# water-meter-v1.net
KiCad netlist of a schematic drawn in EasyEDA Pro
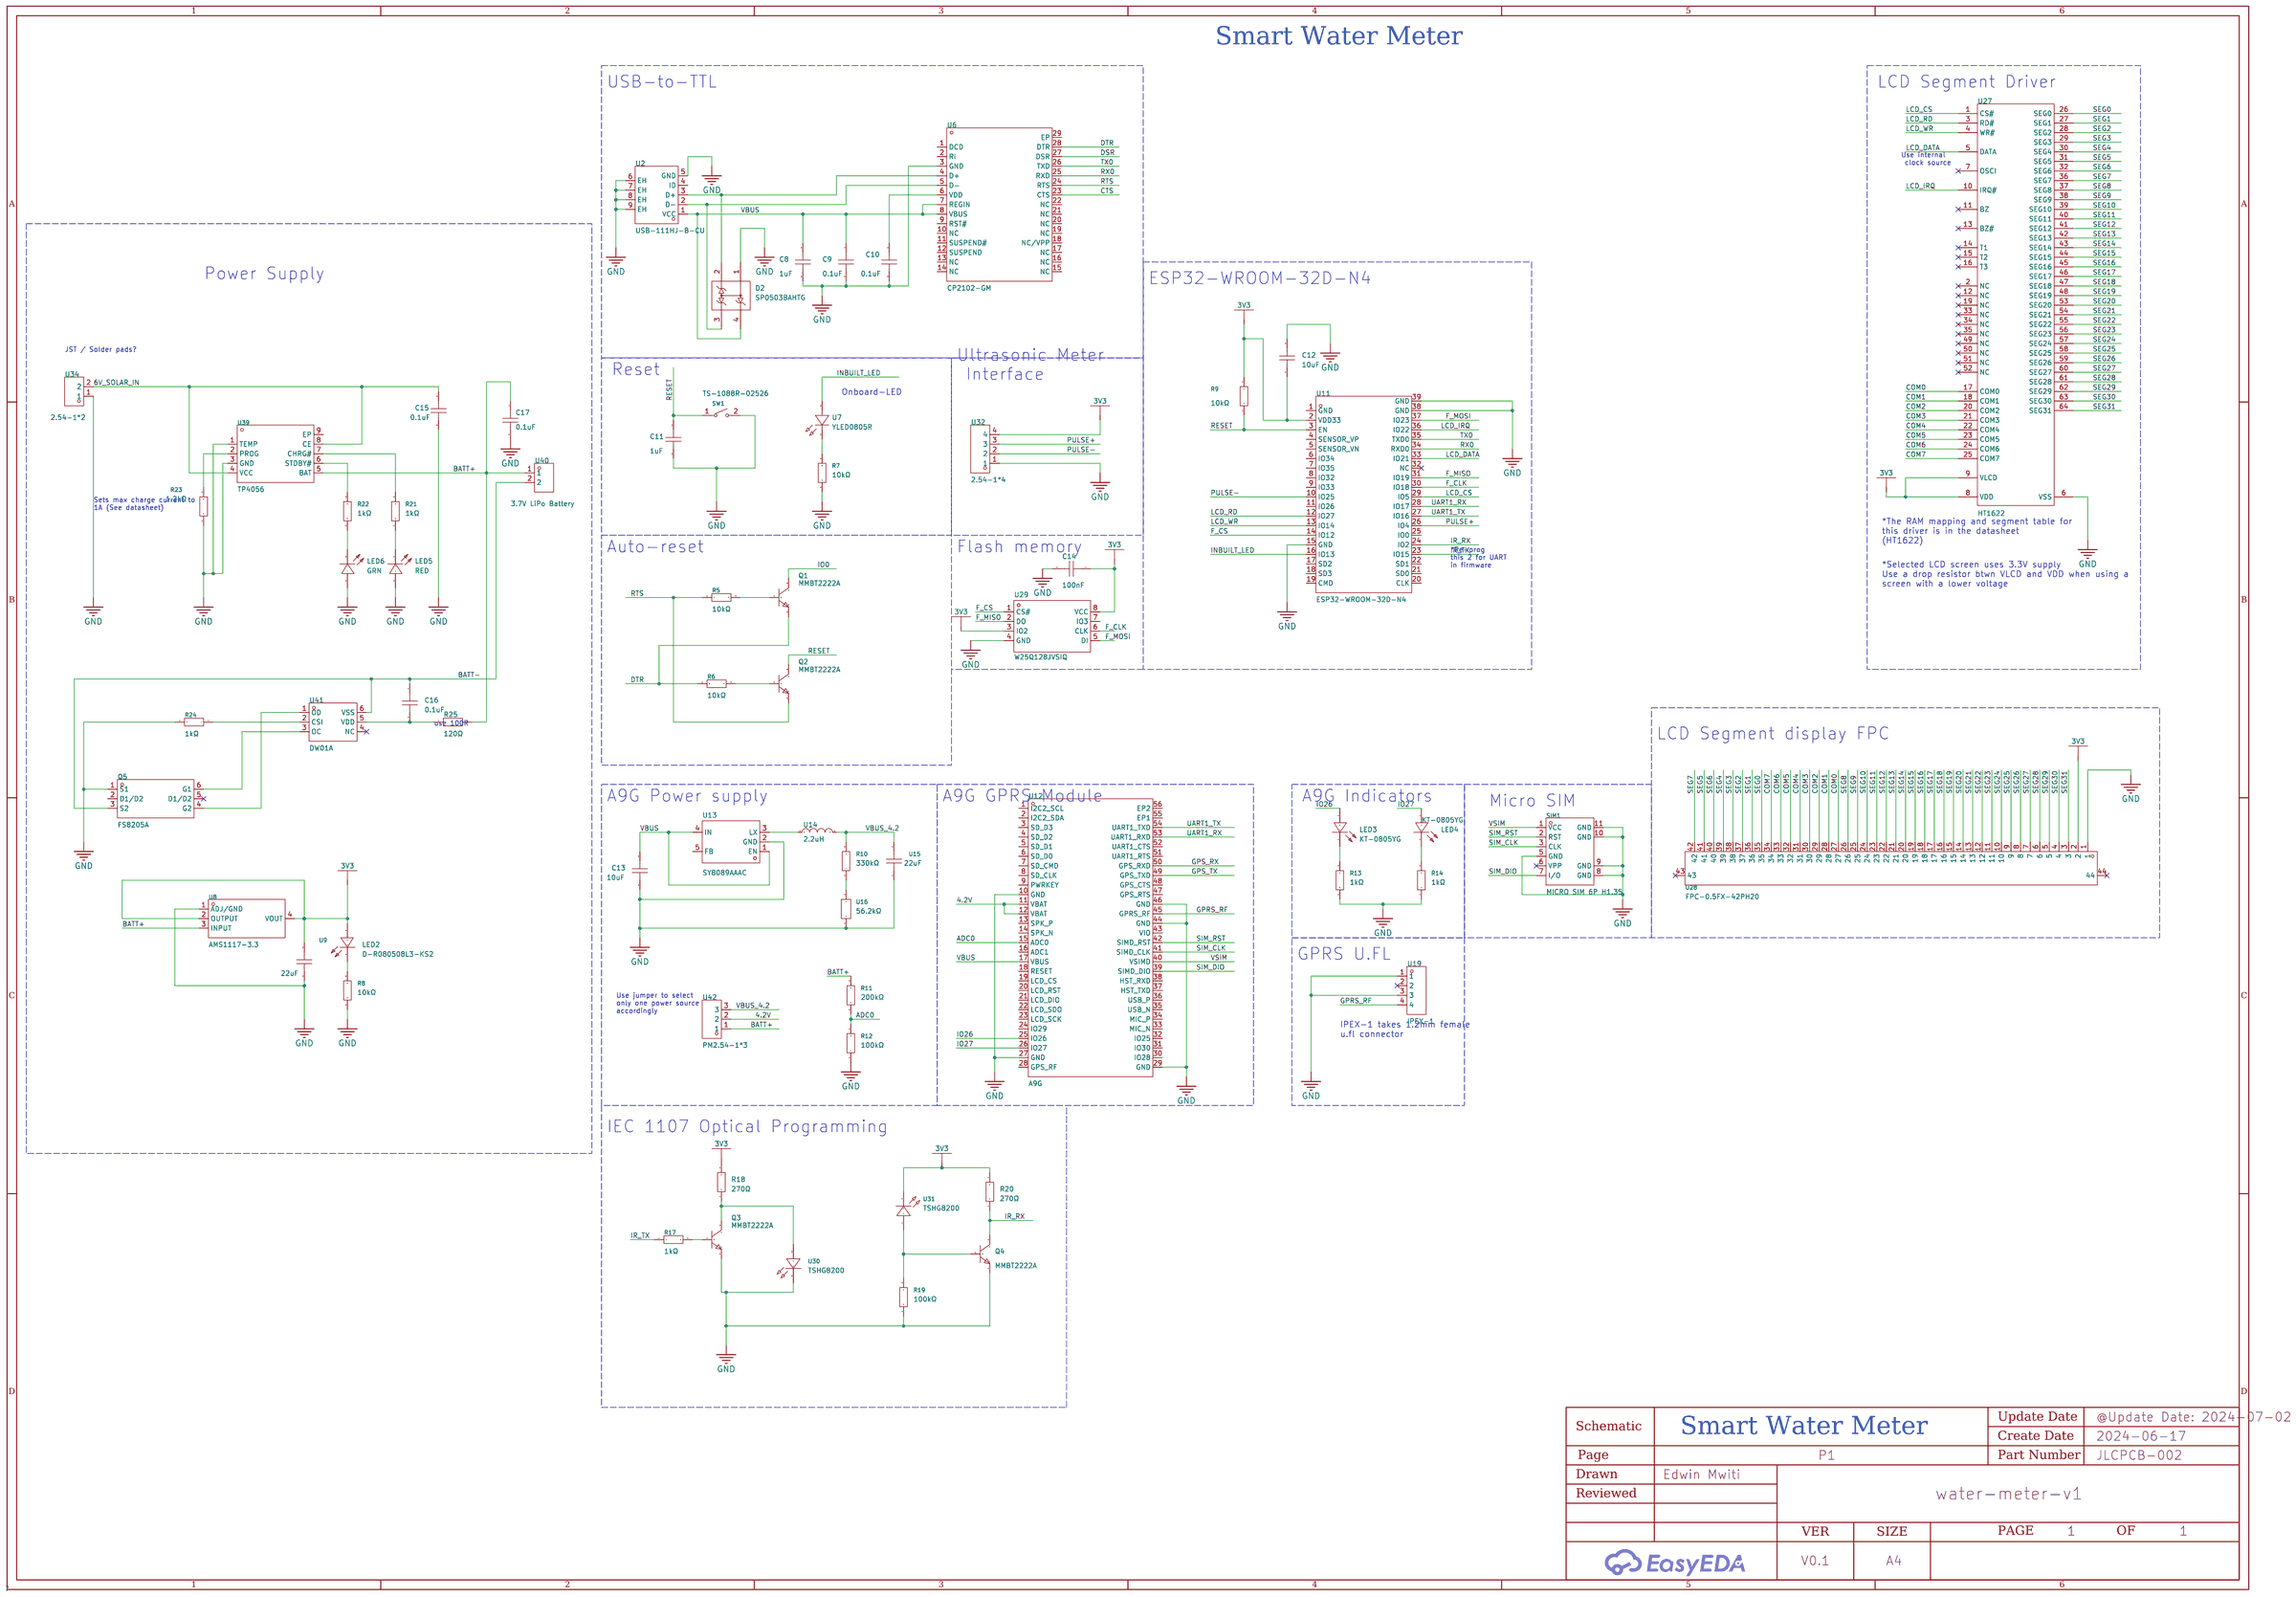
[diagram p0: schematic sheet]

(export (version "E")
  (design (tool "Eeschema 10.0.6"))
  (components
    (comp (ref "C8") (value "1uF") (footprint "easyedapro:C0805") (libsource (lib "easyedapro") (part "CAP")))
    (comp (ref "C9")
      (value "0.1uF")
      (footprint "easyedapro:C0805")
      (libsource (lib "easyedapro") (part "CAP"))
    )
    (comp (ref "C10")
      (value "0.1uF")
      (footprint "easyedapro:C0805")
      (libsource (lib "easyedapro") (part "CAP"))
    )
    (comp (ref "C11")
      (value "1uF")
      (footprint "easyedapro:C0805")
      (libsource (lib "easyedapro") (part "CAP"))
    )
    (comp (ref "C12")
      (value "10uF")
      (footprint "easyedapro:C0805")
      (fields
        (field (name "Manufacturer Part") "C0805X6S106K250NT")
        (field (name "Manufacturer") "SANYEAR(叁叶源)")
      )
      (libsource (lib "easyedapro") (part "C0805X6S106K250NT"))
    )
    (comp (ref "C13")
      (value "10uF")
      (footprint "easyedapro:C0805")
      (fields
        (field (name "Manufacturer Part") "C0805X6S106K250NT")
        (field (name "Manufacturer") "SANYEAR(叁叶源)")
      )
      (libsource (lib "easyedapro") (part "C0805X6S106K250NT"))
    )
    (comp (ref "C14")
      (value "100nF")
      (footprint "easyedapro:C0805")
      (fields
        (field (name "Manufacturer Part") "MBK0805X7R104K500NT")
        (field (name "Manufacturer") "FH-BK(风华邦科)")
      )
      (libsource (lib "easyedapro") (part "0805B104K500NT_C2830721"))
    )
    (comp (ref "C15")
      (value "0.1uF")
      (footprint "easyedapro:C0805")
      (libsource (lib "easyedapro") (part "CAP"))
    )
    (comp (ref "C16")
      (value "0.1uF")
      (footprint "easyedapro:C0805")
      (libsource (lib "easyedapro") (part "CAP"))
    )
    (comp (ref "C17")
      (value "0.1uF")
      (footprint "easyedapro:C0805")
      (libsource (lib "easyedapro") (part "CAP"))
    )
    (comp (ref "D2")
      (value "SP0503BAHTG")
      (footprint "easyedapro:SOT-143-4_L2.9-W1.3-P1.92-LS2.4-BL")
      (description "Type:ESD")
      (fields (field (name "Manufacturer") "TECH PUBLIC(台舟)"))
      (libsource (lib "easyedapro") (part "SP0503BAHTG_C3040626"))
    )
    (comp (ref "LED2")
      (value "D-R080508L3-KS2")
      (footprint "easyedapro:LED0805-RD")
      (description "Emitted Color:Red")
      (fields (field (name "Manufacturer") "ARKLED(方舟)"))
      (libsource (lib "easyedapro") (part "D-R080508L3-KS2"))
    )
    (comp (ref "LED3")
      (value "KT-0805YG")
      (footprint "easyedapro:LED0805-R-RD")
      (description "Emitted Color:Green-yellow")
      (fields (field (name "Manufacturer") "KENTO"))
      (libsource (lib "easyedapro") (part "Yellow green 0805"))
    )
    (comp (ref "LED4")
      (value "KT-0805YG")
      (footprint "easyedapro:LED0805-R-RD")
      (description "Emitted Color:Green-yellow")
      (fields (field (name "Manufacturer") "KENTO"))
      (libsource (lib "easyedapro") (part "Yellow green 0805"))
    )
    (comp (ref "LED5")
      (value "RED")
      (footprint "easyedapro:LED0805-RD")
      (description "Emitted Color:Red")
      (fields (field (name "Manufacturer") "ARKLED(方舟)"))
      (libsource (lib "easyedapro") (part "D-R080508L3-KS2"))
    )
    (comp (ref "LED6")
      (value "GRN")
      (footprint "easyedapro:LED0805-R-RD_GREEN")
      (description "Emitted Color:Green-yellow")
      (fields (field (name "Manufacturer") "yongyu(永裕光电)"))
      (libsource (lib "easyedapro") (part "SZYY0805YG"))
    )
    (comp (ref "Q1")
      (value "MMBT2222A")
      (footprint "easyedapro:SOT-23-3_L2.9-W1.3-P1.90-LS2.4-BR")
      (fields (field (name "Manufacturer") "WPMtek(维攀)"))
      (libsource (lib "easyedapro") (part "MMBT2222A_C2688232"))
    )
    (comp (ref "Q2")
      (value "MMBT2222A")
      (footprint "easyedapro:SOT-23-3_L2.9-W1.3-P1.90-LS2.4-BR")
      (fields (field (name "Manufacturer") "WPMtek(维攀)"))
      (libsource (lib "easyedapro") (part "MMBT2222A_C2688232"))
    )
    (comp (ref "Q3")
      (value "MMBT2222A")
      (footprint "easyedapro:SOT-23-3_L2.9-W1.3-P1.90-LS2.4-BR")
      (fields (field (name "Manufacturer") "WPMtek(维攀)"))
      (libsource (lib "easyedapro") (part "MMBT2222A_C2688232"))
    )
    (comp (ref "Q4")
      (value "MMBT2222A")
      (footprint "easyedapro:SOT-23-3_L2.9-W1.3-P1.90-LS2.4-BR")
      (fields (field (name "Manufacturer") "WPMtek(维攀)"))
      (libsource (lib "easyedapro") (part "MMBT2222A_C2688232"))
    )
    (comp (ref "Q5")
      (value "FS8205A")
      (footprint "easyedapro:SOT-23-6_L2.9-W1.6-P0.95-LS2.8-BR")
      (fields (field (name "Manufacturer") "FUXINSEMI(富芯森美)"))
      (libsource (lib "easyedapro") (part "FS8205A_C908265"))
    )
    (comp (ref "R5")
      (value "10kΩ")
      (footprint "easyedapro:R0805")
      (fields (field (name "Manufacturer Part") "RMC080510K1%N") (field (name "Manufacturer") "Tyohm(幸亚电阻)"))
      (libsource (lib "easyedapro") (part "RMC080510K1%N"))
    )
    (comp (ref "R6")
      (value "10kΩ")
      (footprint "easyedapro:R0805")
      (fields (field (name "Manufacturer Part") "RMC080510K1%N") (field (name "Manufacturer") "Tyohm(幸亚电阻)"))
      (libsource (lib "easyedapro") (part "RMC080510K1%N"))
    )
    (comp (ref "R7")
      (value "10kΩ")
      (footprint "easyedapro:R0805")
      (fields (field (name "Manufacturer Part") "RMC080510K1%N") (field (name "Manufacturer") "Tyohm(幸亚电阻)"))
      (libsource (lib "easyedapro") (part "RMC080510K1%N"))
    )
    (comp (ref "R8")
      (value "10kΩ")
      (footprint "easyedapro:R0805")
      (fields (field (name "Manufacturer Part") "RMC080510K1%N") (field (name "Manufacturer") "Tyohm(幸亚电阻)"))
      (libsource (lib "easyedapro") (part "RMC080510K1%N"))
    )
    (comp (ref "R9")
      (value "10kΩ")
      (footprint "easyedapro:R0805")
      (fields (field (name "Manufacturer Part") "RMC080510K1%N") (field (name "Manufacturer") "Tyohm(幸亚电阻)"))
      (libsource (lib "easyedapro") (part "RMC080510K1%N"))
    )
    (comp (ref "R10")
      (value "330kΩ")
      (footprint "easyedapro:R0805")
      (fields (field (name "Manufacturer Part") "RMC0805330K5%N") (field (name "Manufacturer") "Tyohm(幸亚电阻)"))
      (libsource (lib "easyedapro") (part "RMC0805330K5%N"))
    )
    (comp (ref "R11")
      (value "200kΩ")
      (footprint "easyedapro:R0805")
      (fields (field (name "Manufacturer Part") "RMC0805200K1%N") (field (name "Manufacturer") "Tyohm(幸亚电阻)"))
      (libsource (lib "easyedapro") (part "RMC0805200K1%N"))
    )
    (comp (ref "R12")
      (value "100kΩ")
      (footprint "easyedapro:R0805")
      (fields (field (name "Manufacturer Part") "RMC0805100K1%N") (field (name "Manufacturer") "Tyohm(幸亚电阻)"))
      (libsource (lib "easyedapro") (part "RMC0805100K1%N"))
    )
    (comp (ref "R13")
      (value "1kΩ")
      (footprint "easyedapro:R0805")
      (fields (field (name "Manufacturer Part") "RMC08051K1%N") (field (name "Manufacturer") "Tyohm(幸亚电阻)"))
      (libsource (lib "easyedapro") (part "RMC08051K1%N"))
    )
    (comp (ref "R14")
      (value "1kΩ")
      (footprint "easyedapro:R0805")
      (fields (field (name "Manufacturer Part") "RMC08051K1%N") (field (name "Manufacturer") "Tyohm(幸亚电阻)"))
      (libsource (lib "easyedapro") (part "RMC08051K1%N"))
    )
    (comp (ref "R17")
      (value "1kΩ")
      (footprint "easyedapro:R0805")
      (fields (field (name "Manufacturer Part") "RMC08051K5%N") (field (name "Manufacturer") "Tyohm(幸亚电阻)"))
      (libsource (lib "easyedapro") (part "RMC08051K5%N"))
    )
    (comp (ref "R18")
      (value "270Ω")
      (footprint "easyedapro:R0805")
      (fields (field (name "Manufacturer Part") "RC0805JR-07270RL") (field (name "Manufacturer") "YAGEO(国巨)"))
      (libsource (lib "easyedapro") (part "RC0805JR-07270RL"))
    )
    (comp (ref "R19")
      (value "100kΩ")
      (footprint "easyedapro:R0805")
      (fields (field (name "Manufacturer Part") "RMC0805100K1%N") (field (name "Manufacturer") "Tyohm(幸亚电阻)"))
      (libsource (lib "easyedapro") (part "RMC0805100K1%N"))
    )
    (comp (ref "R20")
      (value "270Ω")
      (footprint "easyedapro:R0805")
      (fields (field (name "Manufacturer Part") "RC0805JR-07270RL") (field (name "Manufacturer") "YAGEO(国巨)"))
      (libsource (lib "easyedapro") (part "RC0805JR-07270RL"))
    )
    (comp (ref "R21")
      (value "1kΩ")
      (footprint "easyedapro:R0805")
      (fields (field (name "Manufacturer Part") "RMC08051K5%N") (field (name "Manufacturer") "Tyohm(幸亚电阻)"))
      (libsource (lib "easyedapro") (part "RMC08051K5%N"))
    )
    (comp (ref "R22")
      (value "1kΩ")
      (footprint "easyedapro:R0805")
      (fields (field (name "Manufacturer Part") "RMC08051K5%N") (field (name "Manufacturer") "Tyohm(幸亚电阻)"))
      (libsource (lib "easyedapro") (part "RMC08051K5%N"))
    )
    (comp (ref "R23")
      (value "1.2kΩ")
      (footprint "easyedapro:R0805")
      (fields (field (name "Manufacturer Part") "RMC08051.2K5%N") (field (name "Manufacturer") "Tyohm(幸亚电阻)"))
      (libsource (lib "easyedapro") (part "RMC08051.2K5%N"))
    )
    (comp (ref "R24")
      (value "1kΩ")
      (footprint "easyedapro:R0805")
      (fields (field (name "Manufacturer Part") "RMC08051K5%N") (field (name "Manufacturer") "Tyohm(幸亚电阻)"))
      (libsource (lib "easyedapro") (part "RMC08051K5%N"))
    )
    (comp (ref "R25")
      (value "120Ω")
      (footprint "easyedapro:R0805")
      (fields
        (field (name "Manufacturer Part") "RMC 0805 120R J N")
        (field (name "Manufacturer") "Tyohm(幸亚电阻)")
      )
      (libsource (lib "easyedapro") (part "RMC08051205%N"))
    )
    (comp (ref "SIM1")
      (value "MICRO SIM 6P H1.35")
      (footprint "easyedapro:SIM-SMD_MICRO-SIM-6P-H1.35")
      (fields (field (name "Manufacturer") "SHOU HAN(首韩)"))
      (libsource (lib "easyedapro") (part "MICRO SIM 6P H1.35"))
    )
    (comp (ref "SW1")
      (value "TS-1088R-02526")
      (footprint "easyedapro:SW-SMD_L3.9-W3.0-P4.45")
      (fields (field (name "Manufacturer") "XUNPU(讯普)"))
      (libsource (lib "easyedapro") (part "TS-1088R-02526"))
    )
    (comp (ref "U2")
      (value "USB-111HJ-B-CU")
      (footprint "easyedapro:MICRO-USB-SMD_HOOYA_USB-111HJ-B-CU")
      (description "Number of Contacts:5P")
      (fields (field (name "Manufacturer") "HOOYA(皓宇电子)"))
      (libsource (lib "easyedapro") (part "USB-111HJ-B-CU"))
    )
    (comp (ref "U6")
      (value "CP2102-GM")
      (footprint "easyedapro:QFN-28_L5.0-W5.0-P0.50-TL-EP3.2")
      (fields (field (name "Manufacturer") "SKYWORKS/SILICON LABS(芯科)"))
      (libsource (lib "easyedapro") (part "CP2102-GM"))
    )
    (comp (ref "U7")
      (value "YLED0805R")
      (footprint "easyedapro:LED0805-RD")
      (fields (field (name "Manufacturer") "YONGYUTAI(永裕泰)"))
      (libsource (lib "easyedapro") (part "YLED0805R"))
    )
    (comp (ref "U8")
      (value "AMS1117-3.3")
      (footprint "easyedapro:SOT-223-3_L6.5-W3.4-P2.30-LS7.0-BR")
      (fields (field (name "Manufacturer") "TECH PUBLIC(台舟)"))
      (libsource (lib "easyedapro") (part "AMS1117-3.3_C18212698"))
    )
    (comp (ref "U9")
      (value "22uF")
      (footprint "easyedapro:C0805")
      (fields
        (field (name "Manufacturer Part") "V226M0805X5R100NHP")
        (field (name "Manufacturer") "VIIYONG(微容)")
      )
      (libsource (lib "easyedapro") (part "V226M0805X5R100NHP"))
    )
    (comp (ref "U11")
      (value "ESP32-WROOM-32D-N4")
      (footprint "easyedapro:WIFIM-SMD_39P-L25.5-W18.0-P1.27-BL")
      (fields (field (name "Manufacturer") "ESPRESSIF(乐鑫)"))
      (libsource (lib "easyedapro") (part "ESP32-WROOM-32D"))
    )
    (comp (ref "U12")
      (value "A9G")
      (footprint "easyedapro:GSM-SMD_A9-GSM-GPRSMODULE")
      (fields (field (name "Manufacturer") "Ai-Thinker(安信可)"))
      (libsource (lib "easyedapro") (part "A9G"))
    )
    (comp (ref "U13")
      (value "SY8089AAAC")
      (footprint "easyedapro:SOT-23-5_L3.0-W1.7-P0.95-LS2.8-BR")
      (fields (field (name "Manufacturer") "silergy(矽力杰)"))
      (libsource (lib "easyedapro") (part "SY8089AAAC"))
    )
    (comp (ref "U14")
      (value "2.2uH")
      (footprint "easyedapro:IND-SMD_L4.5-W4.0_SLF0403-1")
      (fields (field (name "Manufacturer Part") "CY43-2.2UH") (field (name "Manufacturer") "SHOU HAN(首韩)"))
      (libsource (lib "easyedapro") (part "CY43-2.2UH"))
    )
    (comp (ref "U15")
      (value "22uF")
      (footprint "easyedapro:C0805")
      (fields
        (field (name "Manufacturer Part") "V226M0805X5R100NHP")
        (field (name "Manufacturer") "VIIYONG(微容)")
      )
      (libsource (lib "easyedapro") (part "V226M0805X5R100NHP"))
    )
    (comp (ref "U16")
      (value "56.2kΩ")
      (footprint "easyedapro:R0805")
      (fields (field (name "Manufacturer Part") "SCR0805F56K2") (field (name "Manufacturer") "VO(翔胜)"))
      (libsource (lib "easyedapro") (part "SCR0805F56K2"))
    )
    (comp (ref "U19")
      (value "IPEX-1")
      (footprint "easyedapro:IPEX-SMD_4P-L2.6-W2.6-LS3.0")
      (description "RF Series:IPEX")
      (fields (field (name "Manufacturer") "Ziisor(致哲)"))
      (libsource (lib "easyedapro") (part "IPEX-1"))
    )
    (comp (ref "U27")
      (value "HT1622")
      (footprint "easyedapro:LQFP-64_L7.0-W7.0-P0.40-LS9.2-BL")
      (fields (field (name "Manufacturer") "HOLTEK(合泰/盛群)"))
      (libsource (lib "easyedapro") (part "HT1622_C46302"))
    )
    (comp (ref "U28")
      (value "FPC-0.5FX-42PH20")
      (footprint "easyedapro:FPC-SMD_42P-P0.50_YUANDI_FPC-0.5FX-42PH20")
      (description "Locking Feature:Clamshell Contact Type:Bottom Contact Number of Contacts:42P Pitch:0.5mm")
      (fields (field (name "Manufacturer") "Yuandi(元迪)"))
      (libsource (lib "easyedapro") (part "FPC-0.5FX-42PH20"))
    )
    (comp (ref "U29")
      (value "W25Q128JVSIQ")
      (footprint "easyedapro:SOIC-8_L5.3-W5.3-P1.27-LS8.0-BL")
      (fields (field (name "Manufacturer") "WINBOND(华邦)"))
      (libsource (lib "easyedapro") (part "W25Q128JVSIQTR"))
    )
    (comp (ref "U30")
      (value "TSHG8200")
      (footprint "easyedapro:LED-TH_BD5.0-P2.54-FD-1")
      (fields (field (name "Manufacturer") "VISHAY(威世)"))
      (libsource (lib "easyedapro") (part "TSHG8200"))
    )
    (comp (ref "U31")
      (value "TSHG8200")
      (footprint "easyedapro:LED-TH_BD5.0-P2.54-FD-1")
      (fields (field (name "Manufacturer") "VISHAY(威世)"))
      (libsource (lib "easyedapro") (part "TSHG8200"))
    )
    (comp (ref "U32")
      (value "2.54-1*4")
      (footprint "easyedapro:HDR-TH_4P-P2.54-V-M-1")
      (description "Pin Structure:1x4P Pitch:2.54mm Number of Rows:Plugin Number of Pins:4P")
      (fields (field (name "Manufacturer") "ZHOURI(洲日)"))
      (libsource (lib "easyedapro") (part "2.54-1*4"))
    )
    (comp (ref "U34")
      (value "2.54-1*2")
      (footprint "easyedapro:HDR-TH_2P-P2.54-V-M")
      (description "Pin Structure:1x2P Pitch:2.54mm Number of Rows:Plugin Number of Pins:2P Contact Plating:Gold")
      (fields (field (name "Manufacturer") "ZHOURI(洲日)"))
      (libsource (lib "easyedapro") (part "2.54-1*2"))
    )
    (comp (ref "U39")
      (value "TP4056")
      (footprint "easyedapro:ESOP-8_L4.9-W3.9-P1.27-LS6.0-BL-EP")
      (fields (field (name "Manufacturer") "TPOWER(天源)"))
      (libsource (lib "easyedapro") (part "TP4056_C382139"))
    )
    (comp (ref "U40")
      (value "3.7V LiPo Battery")
      (footprint "easyedapro:HDR-TH_2P-P2.54-V-M")
      (description "Pin Structure:1x2P Pitch:2.54mm Number of Rows:Plugin Number of Pins:2P Contact Plating:Gold")
      (fields (field (name "Manufacturer") "ZHOURI(洲日)"))
      (libsource (lib "easyedapro") (part "2.54-1*2"))
    )
    (comp (ref "U41")
      (value "DW01A")
      (footprint "easyedapro:SOT-23-6_L2.9-W1.6-P0.95-LS2.8-BL")
      (fields (field (name "Manufacturer") "YONGYUTAI(永裕泰)"))
      (libsource (lib "easyedapro") (part "DW01A_C2927799"))
    )
    (comp (ref "U42")
      (value "PM2.54-1*3")
      (footprint "easyedapro:HDR-TH_3P-P2.54-V-F")
      (fields (field (name "Manufacturer") "ZHOURI(洲日)"))
      (libsource (lib "easyedapro") (part "PM2.54-1*3"))
    )
  )
  (nets
    (net (code "1") (name "/4.2V") (class "Default")
      (node (ref "U12") (pin "11") (pinfunction "VBAT_11") (pintype "unspecified"))
      (node (ref "U12") (pin "12") (pinfunction "VBAT_12") (pintype "unspecified"))
      (node (ref "U42") (pin "2") (pinfunction "2_2") (pintype "unspecified"))
    )
    (net (code "2") (name "/6V_SOLAR_IN") (class "Default")
      (node (ref "C15") (pin "1") (pinfunction "1_1") (pintype "input"))
      (node (ref "U34") (pin "2") (pinfunction "2_2") (pintype "unspecified"))
      (node (ref "U39") (pin "4") (pinfunction "VCC_4") (pintype "input"))
      (node (ref "U39") (pin "8") (pinfunction "CE_8") (pintype "input"))
    )
    (net (code "3") (name "/ADC0") (class "Default")
      (node (ref "R11") (pin "1") (pinfunction "1_1") (pintype "input"))
      (node (ref "R12") (pin "2") (pinfunction "2_2") (pintype "input"))
      (node (ref "U12") (pin "15") (pinfunction "ADC0_15") (pintype "unspecified"))
    )
    (net (code "4") (name "/BATT+") (class "Default")
      (node (ref "C17") (pin "1") (pinfunction "1_1") (pintype "input"))
      (node (ref "R11") (pin "2") (pinfunction "2_2") (pintype "input"))
      (node (ref "R25") (pin "2") (pinfunction "2_2") (pintype "input"))
      (node (ref "U39") (pin "5") (pinfunction "BAT_5") (pintype "input"))
      (node (ref "U40") (pin "1") (pinfunction "1_1") (pintype "unspecified"))
      (node (ref "U42") (pin "1") (pinfunction "1_1") (pintype "unspecified"))
      (node (ref "U8") (pin "3") (pinfunction "INPUT_3") (pintype "input"))
    )
    (net (code "5") (name "/BATT-") (class "Default")
      (node (ref "C16") (pin "1") (pinfunction "1_1") (pintype "input"))
      (node (ref "Q5") (pin "3") (pinfunction "S2_3") (pintype "unspecified"))
      (node (ref "U40") (pin "2") (pinfunction "2_2") (pintype "unspecified"))
      (node (ref "U41") (pin "6") (pinfunction "VSS_6") (pintype "unspecified"))
    )
    (net (code "6") (name "/COM0") (class "Default")
      (node (ref "U27") (pin "17") (pinfunction "COM0_17") (pintype "output"))
      (node (ref "U28") (pin "27") (pinfunction "27_27") (pintype "input"))
    )
    (net (code "7") (name "/COM1") (class "Default")
      (node (ref "U27") (pin "18") (pinfunction "COM1_18") (pintype "output"))
      (node (ref "U28") (pin "28") (pinfunction "28_28") (pintype "input"))
    )
    (net (code "8") (name "/COM2") (class "Default")
      (node (ref "U27") (pin "20") (pinfunction "COM2_20") (pintype "output"))
      (node (ref "U28") (pin "29") (pinfunction "29_29") (pintype "input"))
    )
    (net (code "9") (name "/COM3") (class "Default")
      (node (ref "U27") (pin "21") (pinfunction "COM3_21") (pintype "output"))
      (node (ref "U28") (pin "30") (pinfunction "30_30") (pintype "input"))
    )
    (net (code "10") (name "/COM4") (class "Default")
      (node (ref "U27") (pin "22") (pinfunction "COM4_22") (pintype "output"))
      (node (ref "U28") (pin "31") (pinfunction "31_31") (pintype "input"))
    )
    (net (code "11") (name "/COM5") (class "Default")
      (node (ref "U27") (pin "23") (pinfunction "COM5_23") (pintype "output"))
      (node (ref "U28") (pin "32") (pinfunction "32_32") (pintype "input"))
    )
    (net (code "12") (name "/COM6") (class "Default")
      (node (ref "U27") (pin "24") (pinfunction "COM6_24") (pintype "output"))
      (node (ref "U28") (pin "33") (pinfunction "33_33") (pintype "input"))
    )
    (net (code "13") (name "/COM7") (class "Default")
      (node (ref "U27") (pin "25") (pinfunction "COM7_25") (pintype "output"))
      (node (ref "U28") (pin "34") (pinfunction "34_34") (pintype "input"))
    )
    (net (code "14") (name "/CTS") (class "Default")
      (node (ref "U6") (pin "23") (pinfunction "CTS_23") (pintype "unspecified"))
    )
    (net (code "15") (name "/DSR") (class "Default")
      (node (ref "U6") (pin "27") (pinfunction "DSR_27") (pintype "unspecified"))
    )
    (net (code "16") (name "/DTR") (class "Default")
      (node (ref "Q1") (pin "2") (pinfunction "E_2") (pintype "input"))
      (node (ref "R6") (pin "1") (pinfunction "1_1") (pintype "input"))
      (node (ref "U6") (pin "28") (pinfunction "DTR_28") (pintype "unspecified"))
    )
    (net (code "17") (name "/F_CLK") (class "Default")
      (node (ref "U11") (pin "30") (pinfunction "IO18_30") (pintype "unspecified"))
      (node (ref "U29") (pin "6") (pinfunction "CLK_6") (pintype "unspecified"))
    )
    (net (code "18") (name "/F_CS") (class "Default")
      (node (ref "U11") (pin "14") (pinfunction "IO12_14") (pintype "unspecified"))
      (node (ref "U29") (pin "1") (pinfunction "CS#_1") (pintype "unspecified"))
    )
    (net (code "19") (name "/F_MISO") (class "Default")
      (node (ref "U11") (pin "31") (pinfunction "IO19_31") (pintype "unspecified"))
      (node (ref "U29") (pin "2") (pinfunction "DO_2") (pintype "unspecified"))
    )
    (net (code "20") (name "/F_MOSI") (class "Default")
      (node (ref "U11") (pin "37") (pinfunction "IO23_37") (pintype "unspecified"))
      (node (ref "U29") (pin "5") (pinfunction "DI_5") (pintype "unspecified"))
    )
    (net (code "21") (name "/GPRS_RF") (class "Default")
      (node (ref "U12") (pin "45") (pinfunction "GPRS_RF_45") (pintype "unspecified"))
      (node (ref "U19") (pin "4") (pinfunction "4_4") (pintype "unspecified"))
    )
    (net (code "22") (name "/GPS_RX") (class "Default")
      (node (ref "U12") (pin "50") (pinfunction "GPS_RXD_50") (pintype "unspecified"))
    )
    (net (code "23") (name "/GPS_TX") (class "Default")
      (node (ref "U12") (pin "49") (pinfunction "GPS_TXD_49") (pintype "unspecified"))
    )
    (net (code "24") (name "/INBUILT_LED") (class "Default")
      (node (ref "U11") (pin "16") (pinfunction "IO13_16") (pintype "unspecified"))
      (node (ref "U7") (pin "2") (pinfunction "A_2") (pintype "unspecified"))
    )
    (net (code "25") (name "/IO0") (class "Default")
      (node (ref "Q1") (pin "3") (pinfunction "C_3") (pintype "input"))
    )
    (net (code "26") (name "/IO26") (class "Default")
      (node (ref "LED3") (pin "1") (pinfunction "A_1") (pintype "unspecified"))
      (node (ref "U12") (pin "25") (pinfunction "IO26_25") (pintype "unspecified"))
    )
    (net (code "27") (name "/IO27") (class "Default")
      (node (ref "LED4") (pin "1") (pinfunction "A_1") (pintype "unspecified"))
      (node (ref "U12") (pin "26") (pinfunction "IO27_26") (pintype "unspecified"))
    )
    (net (code "28") (name "/IR_RX") (class "Default")
      (node (ref "Q4") (pin "3") (pinfunction "C_3") (pintype "input"))
      (node (ref "R20") (pin "1") (pinfunction "1_1") (pintype "input"))
      (node (ref "U11") (pin "24") (pinfunction "IO2_24") (pintype "unspecified"))
    )
    (net (code "29") (name "/IR_TX") (class "Default")
      (node (ref "R17") (pin "1") (pinfunction "1_1") (pintype "input"))
      (node (ref "U11") (pin "23") (pinfunction "IO15_23") (pintype "unspecified"))
    )
    (net (code "30") (name "/LCD_CS") (class "Default")
      (node (ref "U11") (pin "29") (pinfunction "IO5_29") (pintype "unspecified"))
      (node (ref "U27") (pin "1") (pinfunction "CS#_1") (pintype "unspecified"))
    )
    (net (code "31") (name "/LCD_DATA") (class "Default")
      (node (ref "U11") (pin "33") (pinfunction "IO21_33") (pintype "unspecified"))
      (node (ref "U27") (pin "5") (pinfunction "DATA_5") (pintype "bidirectional"))
    )
    (net (code "32") (name "/LCD_IRQ") (class "Default")
      (node (ref "U11") (pin "36") (pinfunction "IO22_36") (pintype "unspecified"))
      (node (ref "U27") (pin "10") (pinfunction "IRQ#_10") (pintype "unspecified"))
    )
    (net (code "33") (name "/LCD_RD") (class "Default")
      (node (ref "U11") (pin "12") (pinfunction "IO27_12") (pintype "unspecified"))
      (node (ref "U27") (pin "3") (pinfunction "RD#_3") (pintype "unspecified"))
    )
    (net (code "34") (name "/LCD_WR") (class "Default")
      (node (ref "U11") (pin "13") (pinfunction "IO14_13") (pintype "unspecified"))
      (node (ref "U27") (pin "4") (pinfunction "WR#_4") (pintype "unspecified"))
    )
    (net (code "35") (name "/PULSE+") (class "Default")
      (node (ref "U11") (pin "26") (pinfunction "IO4_26") (pintype "unspecified"))
      (node (ref "U32") (pin "3") (pinfunction "3_3") (pintype "unspecified"))
    )
    (net (code "36") (name "/PULSE-") (class "Default")
      (node (ref "U11") (pin "10") (pinfunction "IO25_10") (pintype "unspecified"))
      (node (ref "U32") (pin "2") (pinfunction "2_2") (pintype "unspecified"))
    )
    (net (code "37") (name "/RESET") (class "Default")
      (node (ref "C11") (pin "1") (pinfunction "1_1") (pintype "input"))
      (node (ref "Q2") (pin "3") (pinfunction "C_3") (pintype "input"))
      (node (ref "R9") (pin "1") (pinfunction "1_1") (pintype "input"))
      (node (ref "SW1") (pin "1") (pinfunction "1_1") (pintype "input"))
      (node (ref "U11") (pin "3") (pinfunction "EN_3") (pintype "unspecified"))
    )
    (net (code "38") (name "/RTS") (class "Default")
      (node (ref "Q2") (pin "2") (pinfunction "E_2") (pintype "input"))
      (node (ref "R5") (pin "1") (pinfunction "1_1") (pintype "input"))
      (node (ref "U6") (pin "24") (pinfunction "RTS_24") (pintype "unspecified"))
    )
    (net (code "39") (name "/RX0") (class "Default")
      (node (ref "U11") (pin "34") (pinfunction "RXD0_34") (pintype "unspecified"))
      (node (ref "U6") (pin "25") (pinfunction "RXD_25") (pintype "unspecified"))
    )
    (net (code "40") (name "/SEG0") (class "Default")
      (node (ref "U27") (pin "26") (pinfunction "SEG0_26") (pintype "output"))
      (node (ref "U28") (pin "35") (pinfunction "35_35") (pintype "input"))
    )
    (net (code "41") (name "/SEG1") (class "Default")
      (node (ref "U27") (pin "27") (pinfunction "SEG1_27") (pintype "output"))
      (node (ref "U28") (pin "36") (pinfunction "36_36") (pintype "input"))
    )
    (net (code "42") (name "/SEG2") (class "Default")
      (node (ref "U27") (pin "28") (pinfunction "SEG2_28") (pintype "output"))
      (node (ref "U28") (pin "37") (pinfunction "37_37") (pintype "input"))
    )
    (net (code "43") (name "/SEG3") (class "Default")
      (node (ref "U27") (pin "29") (pinfunction "SEG3_29") (pintype "output"))
      (node (ref "U28") (pin "38") (pinfunction "38_38") (pintype "input"))
    )
    (net (code "44") (name "/SEG4") (class "Default")
      (node (ref "U27") (pin "30") (pinfunction "SEG4_30") (pintype "output"))
      (node (ref "U28") (pin "39") (pinfunction "39_39") (pintype "input"))
    )
    (net (code "45") (name "/SEG5") (class "Default")
      (node (ref "U27") (pin "31") (pinfunction "SEG5_31") (pintype "output"))
      (node (ref "U28") (pin "41") (pinfunction "41_41") (pintype "input"))
    )
    (net (code "46") (name "/SEG6") (class "Default")
      (node (ref "U27") (pin "32") (pinfunction "SEG6_32") (pintype "output"))
      (node (ref "U28") (pin "40") (pinfunction "40_40") (pintype "input"))
    )
    (net (code "47") (name "/SEG7") (class "Default")
      (node (ref "U27") (pin "36") (pinfunction "SEG7_36") (pintype "output"))
      (node (ref "U28") (pin "42") (pinfunction "42_42") (pintype "input"))
    )
    (net (code "48") (name "/SEG8") (class "Default")
      (node (ref "U27") (pin "37") (pinfunction "SEG8_37") (pintype "output"))
      (node (ref "U28") (pin "26") (pinfunction "26_26") (pintype "input"))
    )
    (net (code "49") (name "/SEG9") (class "Default")
      (node (ref "U27") (pin "38") (pinfunction "SEG9_38") (pintype "output"))
      (node (ref "U28") (pin "25") (pinfunction "25_25") (pintype "input"))
    )
    (net (code "50") (name "/SEG10") (class "Default")
      (node (ref "U27") (pin "39") (pinfunction "SEG10_39") (pintype "output"))
      (node (ref "U28") (pin "24") (pinfunction "24_24") (pintype "input"))
    )
    (net (code "51") (name "/SEG11") (class "Default")
      (node (ref "U27") (pin "40") (pinfunction "SEG11_40") (pintype "output"))
      (node (ref "U28") (pin "23") (pinfunction "23_23") (pintype "input"))
    )
    (net (code "52") (name "/SEG12") (class "Default")
      (node (ref "U27") (pin "41") (pinfunction "SEG12_41") (pintype "output"))
      (node (ref "U28") (pin "22") (pinfunction "22_22") (pintype "input"))
    )
    (net (code "53") (name "/SEG13") (class "Default")
      (node (ref "U27") (pin "42") (pinfunction "SEG13_42") (pintype "output"))
      (node (ref "U28") (pin "21") (pinfunction "21_21") (pintype "input"))
    )
    (net (code "54") (name "/SEG14") (class "Default")
      (node (ref "U27") (pin "43") (pinfunction "SEG14_43") (pintype "output"))
      (node (ref "U28") (pin "20") (pinfunction "20_20") (pintype "input"))
    )
    (net (code "55") (name "/SEG15") (class "Default")
      (node (ref "U27") (pin "44") (pinfunction "SEG15_44") (pintype "output"))
      (node (ref "U28") (pin "19") (pinfunction "19_19") (pintype "input"))
    )
    (net (code "56") (name "/SEG16") (class "Default")
      (node (ref "U27") (pin "45") (pinfunction "SEG16_45") (pintype "output"))
      (node (ref "U28") (pin "18") (pinfunction "18_18") (pintype "input"))
    )
    (net (code "57") (name "/SEG17") (class "Default")
      (node (ref "U27") (pin "46") (pinfunction "SEG17_46") (pintype "output"))
      (node (ref "U28") (pin "17") (pinfunction "17_17") (pintype "input"))
    )
    (net (code "58") (name "/SEG18") (class "Default")
      (node (ref "U27") (pin "47") (pinfunction "SEG18_47") (pintype "output"))
      (node (ref "U28") (pin "16") (pinfunction "16_16") (pintype "input"))
    )
    (net (code "59") (name "/SEG19") (class "Default")
      (node (ref "U27") (pin "48") (pinfunction "SEG19_48") (pintype "output"))
      (node (ref "U28") (pin "15") (pinfunction "15_15") (pintype "input"))
    )
    (net (code "60") (name "/SEG20") (class "Default")
      (node (ref "U27") (pin "53") (pinfunction "SEG20_53") (pintype "output"))
      (node (ref "U28") (pin "14") (pinfunction "14_14") (pintype "input"))
    )
    (net (code "61") (name "/SEG21") (class "Default")
      (node (ref "U27") (pin "54") (pinfunction "SEG21_54") (pintype "output"))
      (node (ref "U28") (pin "13") (pinfunction "13_13") (pintype "input"))
    )
    (net (code "62") (name "/SEG22") (class "Default")
      (node (ref "U27") (pin "55") (pinfunction "SEG22_55") (pintype "output"))
      (node (ref "U28") (pin "12") (pinfunction "12_12") (pintype "input"))
    )
    (net (code "63") (name "/SEG23") (class "Default")
      (node (ref "U27") (pin "56") (pinfunction "SEG23_56") (pintype "output"))
      (node (ref "U28") (pin "11") (pinfunction "11_11") (pintype "input"))
    )
    (net (code "64") (name "/SEG24") (class "Default")
      (node (ref "U27") (pin "57") (pinfunction "SEG24_57") (pintype "output"))
      (node (ref "U28") (pin "10") (pinfunction "10_10") (pintype "input"))
    )
    (net (code "65") (name "/SEG25") (class "Default")
      (node (ref "U27") (pin "58") (pinfunction "SEG25_58") (pintype "output"))
      (node (ref "U28") (pin "9") (pinfunction "9_9") (pintype "input"))
    )
    (net (code "66") (name "/SEG26") (class "Default")
      (node (ref "U27") (pin "59") (pinfunction "SEG26_59") (pintype "output"))
      (node (ref "U28") (pin "8") (pinfunction "8_8") (pintype "input"))
    )
    (net (code "67") (name "/SEG27") (class "Default")
      (node (ref "U27") (pin "60") (pinfunction "SEG27_60") (pintype "output"))
      (node (ref "U28") (pin "7") (pinfunction "7_7") (pintype "input"))
    )
    (net (code "68") (name "/SEG28") (class "Default")
      (node (ref "U27") (pin "61") (pinfunction "SEG28_61") (pintype "output"))
      (node (ref "U28") (pin "6") (pinfunction "6_6") (pintype "input"))
    )
    (net (code "69") (name "/SEG29") (class "Default")
      (node (ref "U27") (pin "62") (pinfunction "SEG29_62") (pintype "output"))
      (node (ref "U28") (pin "5") (pinfunction "5_5") (pintype "input"))
    )
    (net (code "70") (name "/SEG30") (class "Default")
      (node (ref "U27") (pin "63") (pinfunction "SEG30_63") (pintype "output"))
      (node (ref "U28") (pin "4") (pinfunction "4_4") (pintype "input"))
    )
    (net (code "71") (name "/SEG31") (class "Default")
      (node (ref "U27") (pin "64") (pinfunction "SEG31_64") (pintype "output"))
      (node (ref "U28") (pin "3") (pinfunction "3_3") (pintype "input"))
    )
    (net (code "72") (name "/SIM_CLK") (class "Default")
      (node (ref "SIM1") (pin "3") (pinfunction "CLK_3") (pintype "input"))
      (node (ref "U12") (pin "41") (pinfunction "SIMD_CLK_41") (pintype "unspecified"))
    )
    (net (code "73") (name "/SIM_DIO") (class "Default")
      (node (ref "SIM1") (pin "7") (pinfunction "I/O_7") (pintype "input"))
      (node (ref "U12") (pin "39") (pinfunction "SIMD_DIO_39") (pintype "unspecified"))
    )
    (net (code "74") (name "/SIM_RST") (class "Default")
      (node (ref "SIM1") (pin "2") (pinfunction "RST_2") (pintype "input"))
      (node (ref "U12") (pin "42") (pinfunction "SIMD_RST_42") (pintype "unspecified"))
    )
    (net (code "75") (name "/TX0") (class "Default")
      (node (ref "U11") (pin "35") (pinfunction "TXD0_35") (pintype "unspecified"))
      (node (ref "U6") (pin "26") (pinfunction "TXD_26") (pintype "unspecified"))
    )
    (net (code "76") (name "/UART1_RX") (class "Default")
      (node (ref "U11") (pin "28") (pinfunction "IO17_28") (pintype "unspecified"))
      (node (ref "U12") (pin "53") (pinfunction "UART1_RXD_53") (pintype "unspecified"))
    )
    (net (code "77") (name "/UART1_TX") (class "Default")
      (node (ref "U11") (pin "27") (pinfunction "IO16_27") (pintype "unspecified"))
      (node (ref "U12") (pin "54") (pinfunction "UART1_TXD_54") (pintype "unspecified"))
    )
    (net (code "78") (name "/VBUS") (class "Default")
      (node (ref "C13") (pin "2") (pinfunction "2_2") (pintype "input"))
      (node (ref "C8") (pin "1") (pinfunction "1_1") (pintype "input"))
      (node (ref "C9") (pin "1") (pinfunction "1_1") (pintype "input"))
      (node (ref "D2") (pin "4") (pinfunction "4_4") (pintype "input"))
      (node (ref "U12") (pin "17") (pinfunction "VBUS_17") (pintype "unspecified"))
      (node (ref "U13") (pin "1") (pinfunction "EN_1") (pintype "unspecified"))
      (node (ref "U13") (pin "4") (pinfunction "IN_4") (pintype "unspecified"))
      (node (ref "U2") (pin "1") (pinfunction "VCC_1") (pintype "unspecified"))
      (node (ref "U6") (pin "7") (pinfunction "REGIN_7") (pintype "unspecified"))
      (node (ref "U6") (pin "8") (pinfunction "VBUS_8") (pintype "unspecified"))
    )
    (net (code "79") (name "/VBUS_4.2") (class "Default")
      (node (ref "R10") (pin "2") (pinfunction "2_2") (pintype "input"))
      (node (ref "U14") (pin "2") (pinfunction "2_2") (pintype "unspecified"))
      (node (ref "U15") (pin "2") (pinfunction "2_2") (pintype "input"))
      (node (ref "U42") (pin "3") (pinfunction "3_3") (pintype "unspecified"))
    )
    (net (code "80") (name "/VSIM") (class "Default")
      (node (ref "SIM1") (pin "1") (pinfunction "VCC_1") (pintype "input"))
      (node (ref "U12") (pin "40") (pinfunction "VSIMD_40") (pintype "unspecified"))
    )
    (net (code "81") (name "3V3") (class "Default")
      (node (ref "C12") (pin "1") (pinfunction "1_1") (pintype "input"))
      (node (ref "C14") (pin "1") (pinfunction "1_1") (pintype "unspecified"))
      (node (ref "LED2") (pin "2") (pinfunction "A_2") (pintype "unspecified"))
      (node (ref "R18") (pin "2") (pinfunction "2_2") (pintype "input"))
      (node (ref "R20") (pin "2") (pinfunction "2_2") (pintype "input"))
      (node (ref "R9") (pin "2") (pinfunction "2_2") (pintype "input"))
      (node (ref "U11") (pin "2") (pinfunction "VDD33_2") (pintype "unspecified"))
      (node (ref "U27") (pin "8") (pinfunction "VDD_8") (pintype "unspecified"))
      (node (ref "U27") (pin "9") (pinfunction "VLCD_9") (pintype "unspecified"))
      (node (ref "U28") (pin "2") (pinfunction "2_2") (pintype "input"))
      (node (ref "U29") (pin "3") (pinfunction "IO2_3") (pintype "unspecified"))
      (node (ref "U29") (pin "8") (pinfunction "VCC_8") (pintype "unspecified"))
      (node (ref "U31") (pin "2") (pinfunction "C_2") (pintype "input"))
      (node (ref "U32") (pin "4") (pinfunction "4_4") (pintype "unspecified"))
      (node (ref "U8") (pin "2") (pinfunction "OUTPUT_2") (pintype "input"))
      (node (ref "U8") (pin "4") (pinfunction "VOUT_4") (pintype "input"))
      (node (ref "U9") (pin "2") (pinfunction "2_2") (pintype "input"))
    )
    (net (code "82") (name "GND") (class "Default")
      (node (ref "C10") (pin "2") (pinfunction "2_2") (pintype "input"))
      (node (ref "C11") (pin "2") (pinfunction "2_2") (pintype "input"))
      (node (ref "C12") (pin "2") (pinfunction "2_2") (pintype "input"))
      (node (ref "C13") (pin "1") (pinfunction "1_1") (pintype "input"))
      (node (ref "C14") (pin "2") (pinfunction "2_2") (pintype "unspecified"))
      (node (ref "C15") (pin "2") (pinfunction "2_2") (pintype "input"))
      (node (ref "C17") (pin "2") (pinfunction "2_2") (pintype "input"))
      (node (ref "C8") (pin "2") (pinfunction "2_2") (pintype "input"))
      (node (ref "C9") (pin "2") (pinfunction "2_2") (pintype "input"))
      (node (ref "D2") (pin "1") (pinfunction "1_1") (pintype "input"))
      (node (ref "LED5") (pin "2") (pinfunction "A_2") (pintype "unspecified"))
      (node (ref "LED6") (pin "1") (pinfunction "+_1") (pintype "unspecified"))
      (node (ref "Q3") (pin "2") (pinfunction "E_2") (pintype "input"))
      (node (ref "Q4") (pin "2") (pinfunction "E_2") (pintype "input"))
      (node (ref "Q5") (pin "1") (pinfunction "S1_1") (pintype "unspecified"))
      (node (ref "R12") (pin "1") (pinfunction "1_1") (pintype "input"))
      (node (ref "R13") (pin "1") (pinfunction "1_1") (pintype "input"))
      (node (ref "R14") (pin "1") (pinfunction "1_1") (pintype "input"))
      (node (ref "R19") (pin "1") (pinfunction "1_1") (pintype "input"))
      (node (ref "R23") (pin "1") (pinfunction "1_1") (pintype "input"))
      (node (ref "R24") (pin "2") (pinfunction "2_2") (pintype "input"))
      (node (ref "R7") (pin "1") (pinfunction "1_1") (pintype "input"))
      (node (ref "R8") (pin "1") (pinfunction "1_1") (pintype "input"))
      (node (ref "SIM1") (pin "10") (pinfunction "GND_10") (pintype "input"))
      (node (ref "SIM1") (pin "11") (pinfunction "GND_11") (pintype "input"))
      (node (ref "SIM1") (pin "5") (pinfunction "GND_5") (pintype "input"))
      (node (ref "SIM1") (pin "8") (pinfunction "GND_8") (pintype "input"))
      (node (ref "SIM1") (pin "9") (pinfunction "GND_9") (pintype "input"))
      (node (ref "SW1") (pin "2") (pinfunction "2_2") (pintype "input"))
      (node (ref "U11") (pin "15") (pinfunction "GND_15") (pintype "unspecified"))
      (node (ref "U11") (pin "38") (pinfunction "GND_38") (pintype "unspecified"))
      (node (ref "U11") (pin "39") (pinfunction "GND_39") (pintype "unspecified"))
      (node (ref "U12") (pin "10") (pinfunction "GND_10") (pintype "unspecified"))
      (node (ref "U12") (pin "27") (pinfunction "GND_27") (pintype "unspecified"))
      (node (ref "U12") (pin "29") (pinfunction "GND_29") (pintype "unspecified"))
      (node (ref "U12") (pin "44") (pinfunction "GND_44") (pintype "unspecified"))
      (node (ref "U12") (pin "46") (pinfunction "GND_46") (pintype "unspecified"))
      (node (ref "U13") (pin "2") (pinfunction "GND_2") (pintype "unspecified"))
      (node (ref "U15") (pin "1") (pinfunction "1_1") (pintype "input"))
      (node (ref "U16") (pin "1") (pinfunction "1_1") (pintype "input"))
      (node (ref "U19") (pin "1") (pinfunction "1_1") (pintype "unspecified"))
      (node (ref "U19") (pin "3") (pinfunction "3_3") (pintype "unspecified"))
      (node (ref "U2") (pin "5") (pinfunction "GND_5") (pintype "unspecified"))
      (node (ref "U2") (pin "6") (pinfunction "EH_6") (pintype "unspecified"))
      (node (ref "U2") (pin "7") (pinfunction "EH_7") (pintype "unspecified"))
      (node (ref "U2") (pin "8") (pinfunction "EH_8") (pintype "unspecified"))
      (node (ref "U2") (pin "9") (pinfunction "EH_9") (pintype "unspecified"))
      (node (ref "U27") (pin "6") (pinfunction "VSS_6") (pintype "unspecified"))
      (node (ref "U28") (pin "1") (pinfunction "1_1") (pintype "input"))
      (node (ref "U29") (pin "4") (pinfunction "GND_4") (pintype "unspecified"))
      (node (ref "U30") (pin "2") (pinfunction "C_2") (pintype "input"))
      (node (ref "U32") (pin "1") (pinfunction "1_1") (pintype "unspecified"))
      (node (ref "U34") (pin "1") (pinfunction "1_1") (pintype "unspecified"))
      (node (ref "U39") (pin "1") (pinfunction "TEMP_1") (pintype "input"))
      (node (ref "U39") (pin "3") (pinfunction "GND_3") (pintype "input"))
      (node (ref "U6") (pin "3") (pinfunction "GND_3") (pintype "unspecified"))
      (node (ref "U8") (pin "1") (pinfunction "ADJ/GND_1") (pintype "input"))
      (node (ref "U9") (pin "1") (pinfunction "1_1") (pintype "input"))
    )
    (net (code "83") (name "Net-(LED2-K)") (class "Default")
      (node (ref "LED2") (pin "1") (pinfunction "K_1") (pintype "unspecified"))
      (node (ref "R8") (pin "2") (pinfunction "2_2") (pintype "input"))
    )
    (net (code "84") (name "Net-(LED3-K)") (class "Default")
      (node (ref "LED3") (pin "2") (pinfunction "K_2") (pintype "unspecified"))
      (node (ref "R13") (pin "2") (pinfunction "2_2") (pintype "input"))
    )
    (net (code "85") (name "Net-(LED4-K)") (class "Default")
      (node (ref "LED4") (pin "2") (pinfunction "K_2") (pintype "unspecified"))
      (node (ref "R14") (pin "2") (pinfunction "2_2") (pintype "input"))
    )
    (net (code "86") (name "Net-(LED5-K)") (class "Default")
      (node (ref "LED5") (pin "1") (pinfunction "K_1") (pintype "unspecified"))
      (node (ref "R21") (pin "1") (pinfunction "1_1") (pintype "input"))
    )
    (net (code "87") (name "Net-(LED6--)") (class "Default")
      (node (ref "LED6") (pin "2") (pinfunction "-_2") (pintype "unspecified"))
      (node (ref "R22") (pin "1") (pinfunction "1_1") (pintype "input"))
    )
    (net (code "88") (name "Net-(Q1-B)") (class "Default")
      (node (ref "Q1") (pin "1") (pinfunction "B_1") (pintype "input"))
      (node (ref "R5") (pin "2") (pinfunction "2_2") (pintype "input"))
    )
    (net (code "89") (name "Net-(Q2-B)") (class "Default")
      (node (ref "Q2") (pin "1") (pinfunction "B_1") (pintype "input"))
      (node (ref "R6") (pin "2") (pinfunction "2_2") (pintype "input"))
    )
    (net (code "90") (name "Net-(Q3-B)") (class "Default")
      (node (ref "Q3") (pin "1") (pinfunction "B_1") (pintype "input"))
      (node (ref "R17") (pin "2") (pinfunction "2_2") (pintype "input"))
    )
    (net (code "91") (name "Net-(Q3-C)") (class "Default")
      (node (ref "Q3") (pin "3") (pinfunction "C_3") (pintype "input"))
      (node (ref "R18") (pin "1") (pinfunction "1_1") (pintype "input"))
      (node (ref "U30") (pin "1") (pinfunction "A_1") (pintype "input"))
    )
    (net (code "92") (name "Net-(Q4-B)") (class "Default")
      (node (ref "Q4") (pin "1") (pinfunction "B_1") (pintype "input"))
      (node (ref "R19") (pin "2") (pinfunction "2_2") (pintype "input"))
      (node (ref "U31") (pin "1") (pinfunction "A_1") (pintype "input"))
    )
    (net (code "93") (name "Net-(Q5-G1)") (class "Default")
      (node (ref "Q5") (pin "6") (pinfunction "G1_6") (pintype "unspecified"))
      (node (ref "U41") (pin "3") (pinfunction "OC_3") (pintype "unspecified"))
    )
    (net (code "94") (name "Net-(Q5-G2)") (class "Default")
      (node (ref "Q5") (pin "4") (pinfunction "G2_4") (pintype "unspecified"))
      (node (ref "U41") (pin "1") (pinfunction "OD_1") (pintype "unspecified"))
    )
    (net (code "95") (name "Net-(R10-Pad1)") (class "Default")
      (node (ref "R10") (pin "1") (pinfunction "1_1") (pintype "input"))
      (node (ref "U16") (pin "2") (pinfunction "2_2") (pintype "input"))
    )
    (net (code "96") (name "Net-(U2-D+)") (class "Default")
      (node (ref "D2") (pin "2") (pinfunction "2_2") (pintype "input"))
      (node (ref "U2") (pin "3") (pinfunction "D+_3") (pintype "unspecified"))
      (node (ref "U6") (pin "4") (pinfunction "D+_4") (pintype "unspecified"))
    )
    (net (code "97") (name "Net-(U2-D-)") (class "Default")
      (node (ref "D2") (pin "3") (pinfunction "3_3") (pintype "input"))
      (node (ref "U2") (pin "2") (pinfunction "D-_2") (pintype "unspecified"))
      (node (ref "U6") (pin "5") (pinfunction "D-_5") (pintype "unspecified"))
    )
    (net (code "98") (name "Net-(U6-VDD)") (class "Default")
      (node (ref "C10") (pin "1") (pinfunction "1_1") (pintype "input"))
      (node (ref "U6") (pin "6") (pinfunction "VDD_6") (pintype "unspecified"))
    )
    (net (code "99") (name "Net-(U7-K)") (class "Default")
      (node (ref "R7") (pin "2") (pinfunction "2_2") (pintype "input"))
      (node (ref "U7") (pin "1") (pinfunction "K_1") (pintype "unspecified"))
    )
    (net (code "100") (name "Net-(U13-LX)") (class "Default")
      (node (ref "U13") (pin "3") (pinfunction "LX_3") (pintype "unspecified"))
      (node (ref "U14") (pin "1") (pinfunction "1_1") (pintype "unspecified"))
    )
    (net (code "101") (name "Net-(U39-CHRG#)") (class "Default")
      (node (ref "R21") (pin "2") (pinfunction "2_2") (pintype "input"))
      (node (ref "U39") (pin "7") (pinfunction "CHRG#_7") (pintype "input"))
    )
    (net (code "102") (name "Net-(U39-PROG)") (class "Default")
      (node (ref "R23") (pin "2") (pinfunction "2_2") (pintype "input"))
      (node (ref "U39") (pin "2") (pinfunction "PROG_2") (pintype "input"))
    )
    (net (code "103") (name "Net-(U39-STDBY#)") (class "Default")
      (node (ref "R22") (pin "2") (pinfunction "2_2") (pintype "input"))
      (node (ref "U39") (pin "6") (pinfunction "STDBY#_6") (pintype "input"))
    )
    (net (code "104") (name "Net-(U41-CSI)") (class "Default")
      (node (ref "R24") (pin "1") (pinfunction "1_1") (pintype "input"))
      (node (ref "U41") (pin "2") (pinfunction "CSI_2") (pintype "unspecified"))
    )
    (net (code "105") (name "Net-(U41-VDD)") (class "Default")
      (node (ref "C16") (pin "2") (pinfunction "2_2") (pintype "input"))
      (node (ref "R25") (pin "1") (pinfunction "1_1") (pintype "input"))
      (node (ref "U41") (pin "5") (pinfunction "VDD_5") (pintype "unspecified"))
    )
    (net (code "106") (name "unconnected-(Q5-D1{slash}D2-Pad2)") (class "Default")
      (node (ref "Q5") (pin "2") (pinfunction "D1/D2_2") (pintype "unspecified"))
    )
    (net (code "107") (name "unconnected-(Q5-D1{slash}D2-Pad5)") (class "Default")
      (node (ref "Q5") (pin "5") (pinfunction "D1/D2_5") (pintype "unspecified+no_connect"))
    )
    (net (code "108") (name "unconnected-(SIM1-VPP-Pad6)") (class "Default")
      (node (ref "SIM1") (pin "6") (pinfunction "VPP_6") (pintype "input+no_connect"))
    )
    (net (code "109") (name "unconnected-(U2-ID-Pad4)") (class "Default")
      (node (ref "U2") (pin "4") (pinfunction "ID_4") (pintype "unspecified"))
    )
    (net (code "110") (name "unconnected-(U6-DCD-Pad1)") (class "Default")
      (node (ref "U6") (pin "1") (pinfunction "DCD_1") (pintype "unspecified"))
    )
    (net (code "111") (name "unconnected-(U6-EP-Pad29)") (class "Default")
      (node (ref "U6") (pin "29") (pinfunction "EP_29") (pintype "unspecified"))
    )
    (net (code "112") (name "unconnected-(U6-NC-Pad10)") (class "Default")
      (node (ref "U6") (pin "10") (pinfunction "NC_10") (pintype "unspecified"))
    )
    (net (code "113") (name "unconnected-(U6-NC-Pad13)") (class "Default")
      (node (ref "U6") (pin "13") (pinfunction "NC_13") (pintype "unspecified"))
    )
    (net (code "114") (name "unconnected-(U6-NC-Pad14)") (class "Default")
      (node (ref "U6") (pin "14") (pinfunction "NC_14") (pintype "unspecified"))
    )
    (net (code "115") (name "unconnected-(U6-NC-Pad15)") (class "Default")
      (node (ref "U6") (pin "15") (pinfunction "NC_15") (pintype "unspecified"))
    )
    (net (code "116") (name "unconnected-(U6-NC-Pad16)") (class "Default")
      (node (ref "U6") (pin "16") (pinfunction "NC_16") (pintype "unspecified"))
    )
    (net (code "117") (name "unconnected-(U6-NC-Pad17)") (class "Default")
      (node (ref "U6") (pin "17") (pinfunction "NC_17") (pintype "unspecified"))
    )
    (net (code "118") (name "unconnected-(U6-NC-Pad19)") (class "Default")
      (node (ref "U6") (pin "19") (pinfunction "NC_19") (pintype "unspecified"))
    )
    (net (code "119") (name "unconnected-(U6-NC-Pad20)") (class "Default")
      (node (ref "U6") (pin "20") (pinfunction "NC_20") (pintype "unspecified"))
    )
    (net (code "120") (name "unconnected-(U6-NC-Pad21)") (class "Default")
      (node (ref "U6") (pin "21") (pinfunction "NC_21") (pintype "unspecified"))
    )
    (net (code "121") (name "unconnected-(U6-NC-Pad22)") (class "Default")
      (node (ref "U6") (pin "22") (pinfunction "NC_22") (pintype "unspecified"))
    )
    (net (code "122") (name "unconnected-(U6-NC{slash}VPP-Pad18)") (class "Default")
      (node (ref "U6") (pin "18") (pinfunction "NC/VPP_18") (pintype "unspecified"))
    )
    (net (code "123") (name "unconnected-(U6-RI-Pad2)") (class "Default")
      (node (ref "U6") (pin "2") (pinfunction "RI_2") (pintype "unspecified"))
    )
    (net (code "124") (name "unconnected-(U6-RST#-Pad9)") (class "Default")
      (node (ref "U6") (pin "9") (pinfunction "RST#_9") (pintype "unspecified"))
    )
    (net (code "125") (name "unconnected-(U6-SUSPEND#-Pad11)") (class "Default")
      (node (ref "U6") (pin "11") (pinfunction "SUSPEND#_11") (pintype "unspecified"))
    )
    (net (code "126") (name "unconnected-(U6-SUSPEND-Pad12)") (class "Default")
      (node (ref "U6") (pin "12") (pinfunction "SUSPEND_12") (pintype "unspecified"))
    )
    (net (code "127") (name "unconnected-(U11-CLK-Pad20)") (class "Default")
      (node (ref "U11") (pin "20") (pinfunction "CLK_20") (pintype "unspecified"))
    )
    (net (code "128") (name "unconnected-(U11-CMD-Pad19)") (class "Default")
      (node (ref "U11") (pin "19") (pinfunction "CMD_19") (pintype "unspecified"))
    )
    (net (code "129") (name "unconnected-(U11-GND-Pad1)") (class "Default")
      (node (ref "U11") (pin "1") (pinfunction "GND_1") (pintype "unspecified"))
    )
    (net (code "130") (name "unconnected-(U11-IO0-Pad25)") (class "Default")
      (node (ref "U11") (pin "25") (pinfunction "IO0_25") (pintype "unspecified"))
    )
    (net (code "131") (name "unconnected-(U11-IO26-Pad11)") (class "Default")
      (node (ref "U11") (pin "11") (pinfunction "IO26_11") (pintype "unspecified"))
    )
    (net (code "132") (name "unconnected-(U11-IO32-Pad8)") (class "Default")
      (node (ref "U11") (pin "8") (pinfunction "IO32_8") (pintype "unspecified"))
    )
    (net (code "133") (name "unconnected-(U11-IO33-Pad9)") (class "Default")
      (node (ref "U11") (pin "9") (pinfunction "IO33_9") (pintype "unspecified"))
    )
    (net (code "134") (name "unconnected-(U11-IO34-Pad6)") (class "Default")
      (node (ref "U11") (pin "6") (pinfunction "IO34_6") (pintype "unspecified"))
    )
    (net (code "135") (name "unconnected-(U11-IO35-Pad7)") (class "Default")
      (node (ref "U11") (pin "7") (pinfunction "IO35_7") (pintype "unspecified"))
    )
    (net (code "136") (name "unconnected-(U11-NC-Pad32)") (class "Default")
      (node (ref "U11") (pin "32") (pinfunction "NC_32") (pintype "unspecified+no_connect"))
    )
    (net (code "137") (name "unconnected-(U11-SD0-Pad21)") (class "Default")
      (node (ref "U11") (pin "21") (pinfunction "SD0_21") (pintype "unspecified"))
    )
    (net (code "138") (name "unconnected-(U11-SD1-Pad22)") (class "Default")
      (node (ref "U11") (pin "22") (pinfunction "SD1_22") (pintype "unspecified"))
    )
    (net (code "139") (name "unconnected-(U11-SD2-Pad17)") (class "Default")
      (node (ref "U11") (pin "17") (pinfunction "SD2_17") (pintype "unspecified"))
    )
    (net (code "140") (name "unconnected-(U11-SD3-Pad18)") (class "Default")
      (node (ref "U11") (pin "18") (pinfunction "SD3_18") (pintype "unspecified"))
    )
    (net (code "141") (name "unconnected-(U11-SENSOR_VN-Pad5)") (class "Default")
      (node (ref "U11") (pin "5") (pinfunction "SENSOR_VN_5") (pintype "unspecified"))
    )
    (net (code "142") (name "unconnected-(U11-SENSOR_VP-Pad4)") (class "Default")
      (node (ref "U11") (pin "4") (pinfunction "SENSOR_VP_4") (pintype "unspecified"))
    )
    (net (code "143") (name "unconnected-(U12-ADC1-Pad16)") (class "Default")
      (node (ref "U12") (pin "16") (pinfunction "ADC1_16") (pintype "unspecified"))
    )
    (net (code "144") (name "unconnected-(U12-EP1-Pad55)") (class "Default")
      (node (ref "U12") (pin "55") (pinfunction "EP1_55") (pintype "unspecified"))
    )
    (net (code "145") (name "unconnected-(U12-EP2-Pad56)") (class "Default")
      (node (ref "U12") (pin "56") (pinfunction "EP2_56") (pintype "unspecified"))
    )
    (net (code "146") (name "unconnected-(U12-GPS_CTS-Pad48)") (class "Default")
      (node (ref "U12") (pin "48") (pinfunction "GPS_CTS_48") (pintype "unspecified"))
    )
    (net (code "147") (name "unconnected-(U12-GPS_RF-Pad28)") (class "Default")
      (node (ref "U12") (pin "28") (pinfunction "GPS_RF_28") (pintype "unspecified"))
    )
    (net (code "148") (name "unconnected-(U12-GPS_RTS-Pad47)") (class "Default")
      (node (ref "U12") (pin "47") (pinfunction "GPS_RTS_47") (pintype "unspecified"))
    )
    (net (code "149") (name "unconnected-(U12-HST_RXD-Pad38)") (class "Default")
      (node (ref "U12") (pin "38") (pinfunction "HST_RXD_38") (pintype "unspecified"))
    )
    (net (code "150") (name "unconnected-(U12-HST_TXD-Pad37)") (class "Default")
      (node (ref "U12") (pin "37") (pinfunction "HST_TXD_37") (pintype "unspecified"))
    )
    (net (code "151") (name "unconnected-(U12-I2C2_SCL-Pad1)") (class "Default")
      (node (ref "U12") (pin "1") (pinfunction "I2C2_SCL_1") (pintype "unspecified"))
    )
    (net (code "152") (name "unconnected-(U12-I2C2_SDA-Pad2)") (class "Default")
      (node (ref "U12") (pin "2") (pinfunction "I2C2_SDA_2") (pintype "unspecified"))
    )
    (net (code "153") (name "unconnected-(U12-IO25-Pad32)") (class "Default")
      (node (ref "U12") (pin "32") (pinfunction "IO25_32") (pintype "unspecified"))
    )
    (net (code "154") (name "unconnected-(U12-IO28-Pad30)") (class "Default")
      (node (ref "U12") (pin "30") (pinfunction "IO28_30") (pintype "unspecified"))
    )
    (net (code "155") (name "unconnected-(U12-IO29-Pad24)") (class "Default")
      (node (ref "U12") (pin "24") (pinfunction "IO29_24") (pintype "unspecified"))
    )
    (net (code "156") (name "unconnected-(U12-IO30-Pad31)") (class "Default")
      (node (ref "U12") (pin "31") (pinfunction "IO30_31") (pintype "unspecified"))
    )
    (net (code "157") (name "unconnected-(U12-LCD_CS-Pad19)") (class "Default")
      (node (ref "U12") (pin "19") (pinfunction "LCD_CS_19") (pintype "unspecified"))
    )
    (net (code "158") (name "unconnected-(U12-LCD_DIO-Pad21)") (class "Default")
      (node (ref "U12") (pin "21") (pinfunction "LCD_DIO_21") (pintype "unspecified"))
    )
    (net (code "159") (name "unconnected-(U12-LCD_RST-Pad20)") (class "Default")
      (node (ref "U12") (pin "20") (pinfunction "LCD_RST_20") (pintype "unspecified"))
    )
    (net (code "160") (name "unconnected-(U12-LCD_SCK-Pad23)") (class "Default")
      (node (ref "U12") (pin "23") (pinfunction "LCD_SCK_23") (pintype "unspecified"))
    )
    (net (code "161") (name "unconnected-(U12-LCD_SDO-Pad22)") (class "Default")
      (node (ref "U12") (pin "22") (pinfunction "LCD_SDO_22") (pintype "unspecified"))
    )
    (net (code "162") (name "unconnected-(U12-MIC_N-Pad33)") (class "Default")
      (node (ref "U12") (pin "33") (pinfunction "MIC_N_33") (pintype "unspecified"))
    )
    (net (code "163") (name "unconnected-(U12-MIC_P-Pad34)") (class "Default")
      (node (ref "U12") (pin "34") (pinfunction "MIC_P_34") (pintype "unspecified"))
    )
    (net (code "164") (name "unconnected-(U12-PWRKEY-Pad9)") (class "Default")
      (node (ref "U12") (pin "9") (pinfunction "PWRKEY_9") (pintype "unspecified"))
    )
    (net (code "165") (name "unconnected-(U12-RESET-Pad18)") (class "Default")
      (node (ref "U12") (pin "18") (pinfunction "RESET_18") (pintype "unspecified"))
    )
    (net (code "166") (name "unconnected-(U12-SD_CLK-Pad8)") (class "Default")
      (node (ref "U12") (pin "8") (pinfunction "SD_CLK_8") (pintype "unspecified"))
    )
    (net (code "167") (name "unconnected-(U12-SD_CMD-Pad7)") (class "Default")
      (node (ref "U12") (pin "7") (pinfunction "SD_CMD_7") (pintype "unspecified"))
    )
    (net (code "168") (name "unconnected-(U12-SD_D0-Pad6)") (class "Default")
      (node (ref "U12") (pin "6") (pinfunction "SD_D0_6") (pintype "unspecified"))
    )
    (net (code "169") (name "unconnected-(U12-SD_D1-Pad5)") (class "Default")
      (node (ref "U12") (pin "5") (pinfunction "SD_D1_5") (pintype "unspecified"))
    )
    (net (code "170") (name "unconnected-(U12-SD_D2-Pad4)") (class "Default")
      (node (ref "U12") (pin "4") (pinfunction "SD_D2_4") (pintype "unspecified"))
    )
    (net (code "171") (name "unconnected-(U12-SD_D3-Pad3)") (class "Default")
      (node (ref "U12") (pin "3") (pinfunction "SD_D3_3") (pintype "unspecified"))
    )
    (net (code "172") (name "unconnected-(U12-SPK_N-Pad14)") (class "Default")
      (node (ref "U12") (pin "14") (pinfunction "SPK_N_14") (pintype "unspecified"))
    )
    (net (code "173") (name "unconnected-(U12-SPK_P-Pad13)") (class "Default")
      (node (ref "U12") (pin "13") (pinfunction "SPK_P_13") (pintype "unspecified"))
    )
    (net (code "174") (name "unconnected-(U12-UART1_CTS-Pad52)") (class "Default")
      (node (ref "U12") (pin "52") (pinfunction "UART1_CTS_52") (pintype "unspecified"))
    )
    (net (code "175") (name "unconnected-(U12-UART1_RTS-Pad51)") (class "Default")
      (node (ref "U12") (pin "51") (pinfunction "UART1_RTS_51") (pintype "unspecified"))
    )
    (net (code "176") (name "unconnected-(U12-USB_N-Pad35)") (class "Default")
      (node (ref "U12") (pin "35") (pinfunction "USB_N_35") (pintype "unspecified"))
    )
    (net (code "177") (name "unconnected-(U12-USB_P-Pad36)") (class "Default")
      (node (ref "U12") (pin "36") (pinfunction "USB_P_36") (pintype "unspecified"))
    )
    (net (code "178") (name "unconnected-(U12-VIO-Pad43)") (class "Default")
      (node (ref "U12") (pin "43") (pinfunction "VIO_43") (pintype "unspecified"))
    )
    (net (code "179") (name "unconnected-(U13-FB-Pad5)") (class "Default")
      (node (ref "U13") (pin "5") (pinfunction "FB_5") (pintype "unspecified"))
    )
    (net (code "180") (name "unconnected-(U19-Pad2)") (class "Default")
      (node (ref "U19") (pin "2") (pinfunction "2_2") (pintype "unspecified+no_connect"))
    )
    (net (code "181") (name "unconnected-(U27-BZ#-Pad13)") (class "Default")
      (node (ref "U27") (pin "13") (pinfunction "BZ#_13") (pintype "output+no_connect"))
    )
    (net (code "182") (name "unconnected-(U27-BZ-Pad11)") (class "Default")
      (node (ref "U27") (pin "11") (pinfunction "BZ_11") (pintype "output+no_connect"))
    )
    (net (code "183") (name "unconnected-(U27-NC-Pad2)") (class "Default")
      (node (ref "U27") (pin "2") (pinfunction "NC_2") (pintype "unspecified+no_connect"))
    )
    (net (code "184") (name "unconnected-(U27-NC-Pad12)") (class "Default")
      (node (ref "U27") (pin "12") (pinfunction "NC_12") (pintype "unspecified+no_connect"))
    )
    (net (code "185") (name "unconnected-(U27-NC-Pad19)") (class "Default")
      (node (ref "U27") (pin "19") (pinfunction "NC_19") (pintype "unspecified+no_connect"))
    )
    (net (code "186") (name "unconnected-(U27-NC-Pad33)") (class "Default")
      (node (ref "U27") (pin "33") (pinfunction "NC_33") (pintype "unspecified+no_connect"))
    )
    (net (code "187") (name "unconnected-(U27-NC-Pad34)") (class "Default")
      (node (ref "U27") (pin "34") (pinfunction "NC_34") (pintype "unspecified+no_connect"))
    )
    (net (code "188") (name "unconnected-(U27-NC-Pad35)") (class "Default")
      (node (ref "U27") (pin "35") (pinfunction "NC_35") (pintype "unspecified+no_connect"))
    )
    (net (code "189") (name "unconnected-(U27-NC-Pad49)") (class "Default")
      (node (ref "U27") (pin "49") (pinfunction "NC_49") (pintype "unspecified+no_connect"))
    )
    (net (code "190") (name "unconnected-(U27-NC-Pad50)") (class "Default")
      (node (ref "U27") (pin "50") (pinfunction "NC_50") (pintype "unspecified+no_connect"))
    )
    (net (code "191") (name "unconnected-(U27-NC-Pad51)") (class "Default")
      (node (ref "U27") (pin "51") (pinfunction "NC_51") (pintype "unspecified+no_connect"))
    )
    (net (code "192") (name "unconnected-(U27-NC-Pad52)") (class "Default")
      (node (ref "U27") (pin "52") (pinfunction "NC_52") (pintype "unspecified+no_connect"))
    )
    (net (code "193") (name "unconnected-(U27-OSCI-Pad7)") (class "Default")
      (node (ref "U27") (pin "7") (pinfunction "OSCI_7") (pintype "unspecified+no_connect"))
    )
    (net (code "194") (name "unconnected-(U27-T1-Pad14)") (class "Default")
      (node (ref "U27") (pin "14") (pinfunction "T1_14") (pintype "unspecified+no_connect"))
    )
    (net (code "195") (name "unconnected-(U27-T2-Pad15)") (class "Default")
      (node (ref "U27") (pin "15") (pinfunction "T2_15") (pintype "unspecified+no_connect"))
    )
    (net (code "196") (name "unconnected-(U27-T3-Pad16)") (class "Default")
      (node (ref "U27") (pin "16") (pinfunction "T3_16") (pintype "unspecified+no_connect"))
    )
    (net (code "197") (name "unconnected-(U28-Pad43)") (class "Default")
      (node (ref "U28") (pin "43") (pinfunction "43_43") (pintype "input+no_connect"))
    )
    (net (code "198") (name "unconnected-(U28-Pad44)") (class "Default")
      (node (ref "U28") (pin "44") (pinfunction "44_44") (pintype "input+no_connect"))
    )
    (net (code "199") (name "unconnected-(U29-IO3-Pad7)") (class "Default")
      (node (ref "U29") (pin "7") (pinfunction "IO3_7") (pintype "unspecified"))
    )
    (net (code "200") (name "unconnected-(U39-EP-Pad9)") (class "Default")
      (node (ref "U39") (pin "9") (pinfunction "EP_9") (pintype "input"))
    )
    (net (code "201") (name "unconnected-(U41-NC-Pad4)") (class "Default")
      (node (ref "U41") (pin "4") (pinfunction "NC_4") (pintype "unspecified+no_connect"))
    )
  )
)
